# SunS_fixture_EGSE_FTDI.net
KiCad netlist of a schematic drawn in Altium Designer
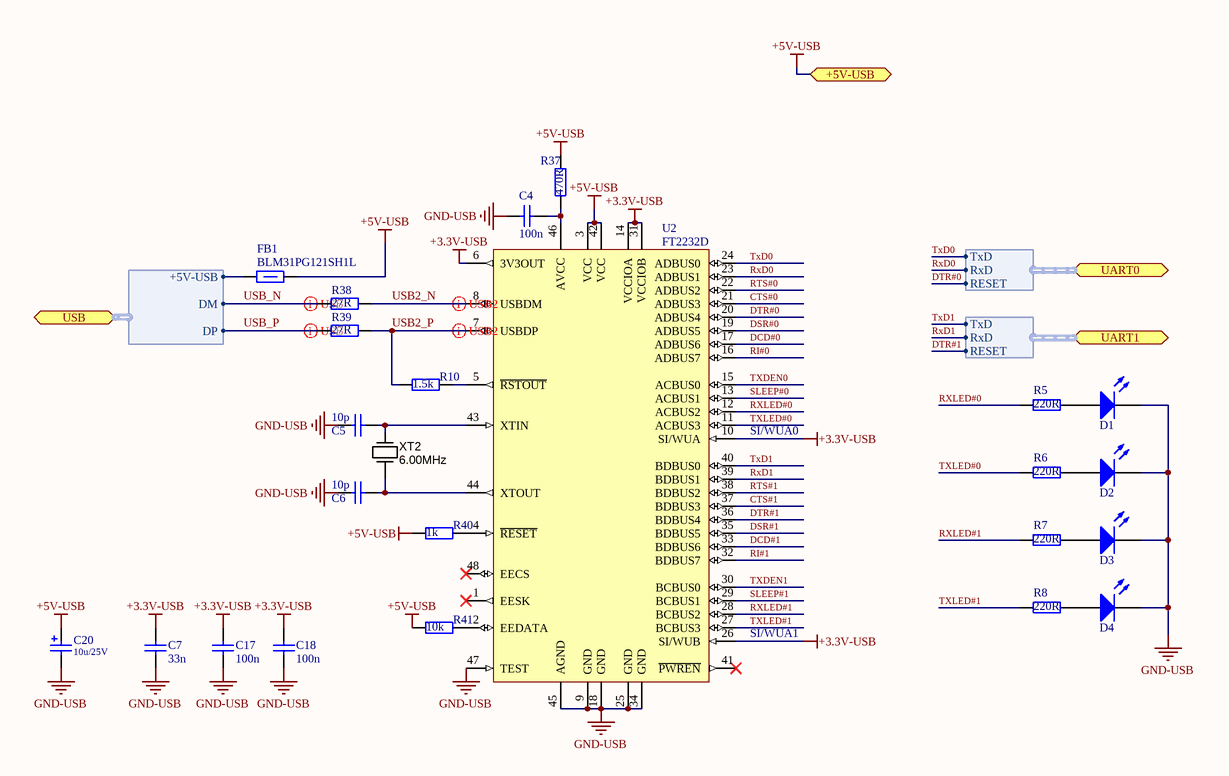
[diagram p0: SunS_fixture_EGSE_FTDI.SchDoc]

(export (version "E")
  (design (tool "Eeschema 10.0.6"))
  (components
    (comp (ref "C4")
      (value "100n")
      (footprint "SMD_Capacitor_0603")
      (description "Cap")
      (libsource (lib "capacitors") (part "Cap"))
    )
    (comp (ref "C5")
      (value "10p")
      (footprint "SMD_Capacitor_0603")
      (description "Cap")
      (libsource (lib "capacitors") (part "Cap"))
    )
    (comp (ref "C6")
      (value "10p")
      (footprint "SMD_Capacitor_0603")
      (description "Cap")
      (libsource (lib "capacitors") (part "Cap"))
    )
    (comp (ref "C7")
      (value "33n")
      (footprint "SMD_Capacitor_0603")
      (description "Cap")
      (libsource (lib "capacitors") (part "Cap"))
    )
    (comp (ref "C17")
      (value "100n")
      (footprint "SMD_Capacitor_0603")
      (description "Cap")
      (libsource (lib "capacitors") (part "Cap"))
    )
    (comp (ref "C18")
      (value "100n")
      (footprint "SMD_Capacitor_0603")
      (description "Cap")
      (libsource (lib "capacitors") (part "Cap"))
    )
    (comp (ref "C20")
      (value "10u/25V")
      (footprint "Tantalum_cap_D")
      (description "Tantalum Capacitor CWR11 10u/22V.")
      (fields
        (field (name "MANUFACTURERPARTNUMBER") "CWR11K(6)106(1)(2)(5)")
        (field (name "MANUFACTURER") "Kemet")
      )
      (libsource (lib "capacitors") (part "TantS_CWR11_10u_25V"))
    )
    (comp (ref "D1")
      (value "LEDX")
      (footprint "LED 0805 RED")
      (description "Typical LED")
      (libsource (lib "diodes") (part "LEDX"))
    )
    (comp (ref "D2")
      (value "LEDX")
      (footprint "LED 0805 RED")
      (description "Typical LED")
      (libsource (lib "diodes") (part "LEDX"))
    )
    (comp (ref "D3")
      (value "LEDX")
      (footprint "LED 0805 RED")
      (description "Typical LED")
      (libsource (lib "diodes") (part "LEDX"))
    )
    (comp (ref "D4")
      (value "LEDX")
      (footprint "LED 0805 RED")
      (description "Typical LED")
      (libsource (lib "diodes") (part "LEDX"))
    )
    (comp (ref "FB1")
      (value "120R/100MHz")
      (footprint "SMD_FerriteBead_1206")
      (description "Ferrite bead, 1206, 0.02HM, 3.5A.")
      (fields (field (name "MANUFACTURER") "Murata") (field (name "MANUFACTURERPARTNUMBER") "BLM31PG121SH1L"))
      (libsource (lib "inductors") (part "BLM31PG121SH1L"))
    )
    (comp (ref "R5")
      (value "220R")
      (footprint "SMD_Resistor_0603")
      (libsource (lib "resistors") (part "Res"))
    )
    (comp (ref "R6")
      (value "220R")
      (footprint "SMD_Resistor_0603")
      (libsource (lib "resistors") (part "Res"))
    )
    (comp (ref "R7")
      (value "220R")
      (footprint "SMD_Resistor_0603")
      (libsource (lib "resistors") (part "Res"))
    )
    (comp (ref "R8")
      (value "220R")
      (footprint "SMD_Resistor_0603")
      (libsource (lib "resistors") (part "Res"))
    )
    (comp (ref "R10")
      (value "1.5k")
      (footprint "SMD_Resistor_0603")
      (libsource (lib "resistors") (part "Res"))
    )
    (comp (ref "R37") (value "470R") (footprint "SMD_Resistor_0603") (libsource (lib "") (part "Res_1")))
    (comp (ref "R38") (value "27R") (footprint "SMD_Resistor_0603") (libsource (lib "") (part "Res_2")))
    (comp (ref "R39") (value "27R") (footprint "SMD_Resistor_0603") (libsource (lib "") (part "Res_2")))
    (comp (ref "R40") (value "1k") (footprint "SMD_Resistor_0603") (libsource (lib "resistors") (part "Res")))
    (comp (ref "R41")
      (value "10k")
      (footprint "SMD_Resistor_0603")
      (libsource (lib "resistors") (part "Res"))
    )
    (comp (ref "U2")
      (value "FT2232D")
      (footprint "LQFP-48_N")
      (description "FT2232D Dual USB to Serial UART/FIFO IC, -40 to +85 degC, 48-pin LQFP")
      (fields (field (name "MANUFACTURER") "FTDI"))
      (libsource (lib "FTDI FT Series") (part "FT2232D"))
    )
    (comp (ref "XT2")
      (value "6.00MHz")
      (footprint "HC49U")
      (description "Resonator Ceramic")
      (fields (field (name "TOLERANCE") "±50ppm"))
      (libsource (lib "crystal") (part "Crystal"))
    )
  )
  (nets
    (net (code "3") (name "+3.3V-USB") (class "Default")
      (node (ref "C17") (pin "1") (pinfunction "1_1") (pintype "passive"))
      (node (ref "C18") (pin "1") (pinfunction "1_1") (pintype "passive"))
      (node (ref "C7") (pin "1") (pinfunction "1_1") (pintype "passive"))
      (node (ref "U2") (pin "10") (pinfunction "SI/WUA_10") (pintype "input"))
      (node (ref "U2") (pin "14") (pinfunction "VCCIOA_14") (pintype "power_in"))
      (node (ref "U2") (pin "26") (pinfunction "SI/WUB_26") (pintype "input"))
      (node (ref "U2") (pin "31") (pinfunction "VCCIOB_31") (pintype "power_in"))
      (node (ref "U2") (pin "6") (pinfunction "3V3OUT_6") (pintype "output"))
    )
    (net (code "4") (name "+5V-USB") (class "Default")
      (node (ref "C20") (pin "1") (pinfunction "1_1") (pintype "passive"))
      (node (ref "FB1") (pin "1") (pinfunction "1_1") (pintype "passive"))
      (node (ref "R37") (pin "2") (pinfunction "2_2") (pintype "passive"))
      (node (ref "R40") (pin "1") (pinfunction "1_1") (pintype "passive"))
      (node (ref "R41") (pin "1") (pinfunction "1_1") (pintype "passive"))
      (node (ref "U2") (pin "3") (pinfunction "VCC_3") (pintype "power_in"))
      (node (ref "U2") (pin "42") (pinfunction "VCC_42") (pintype "power_in"))
    )
    (net (code "5") (name "/CTS#0") (class "Default")
      (node (ref "U2") (pin "21") (pinfunction "ADBUS3_21") (pintype "bidirectional"))
    )
    (net (code "6") (name "/CTS#1") (class "Default")
      (node (ref "U2") (pin "37") (pinfunction "BDBUS3_37") (pintype "bidirectional"))
    )
    (net (code "7") (name "/DCD#0") (class "Default")
      (node (ref "U2") (pin "17") (pinfunction "ADBUS6_17") (pintype "bidirectional"))
    )
    (net (code "8") (name "/DCD#1") (class "Default")
      (node (ref "U2") (pin "33") (pinfunction "BDBUS6_33") (pintype "bidirectional"))
    )
    (net (code "9") (name "/DSR#0") (class "Default")
      (node (ref "U2") (pin "19") (pinfunction "ADBUS5_19") (pintype "bidirectional"))
    )
    (net (code "10") (name "/DSR#1") (class "Default")
      (node (ref "U2") (pin "35") (pinfunction "BDBUS5_35") (pintype "bidirectional"))
    )
    (net (code "11") (name "/DTR#0") (class "Default")
      (node (ref "U2") (pin "20") (pinfunction "ADBUS4_20") (pintype "bidirectional"))
    )
    (net (code "12") (name "/DTR#1") (class "Default")
      (node (ref "U2") (pin "36") (pinfunction "BDBUS4_36") (pintype "bidirectional"))
    )
    (net (code "13") (name "/RI#0") (class "Default")
      (node (ref "U2") (pin "16") (pinfunction "ADBUS7_16") (pintype "bidirectional"))
    )
    (net (code "14") (name "/RI#1") (class "Default")
      (node (ref "U2") (pin "32") (pinfunction "BDBUS7_32") (pintype "bidirectional"))
    )
    (net (code "15") (name "/RTS#0") (class "Default")
      (node (ref "U2") (pin "22") (pinfunction "ADBUS2_22") (pintype "bidirectional"))
    )
    (net (code "16") (name "/RTS#1") (class "Default")
      (node (ref "U2") (pin "38") (pinfunction "BDBUS2_38") (pintype "bidirectional"))
    )
    (net (code "17") (name "/RXLED#0") (class "Default")
      (node (ref "R5") (pin "1") (pinfunction "1_1") (pintype "passive"))
      (node (ref "U2") (pin "12") (pinfunction "ACBUS2_12") (pintype "bidirectional"))
    )
    (net (code "18") (name "/RXLED#1") (class "Default")
      (node (ref "R7") (pin "1") (pinfunction "1_1") (pintype "passive"))
      (node (ref "U2") (pin "28") (pinfunction "BCBUS2_28") (pintype "bidirectional"))
    )
    (net (code "19") (name "/RxD0") (class "Default")
      (node (ref "U2") (pin "23") (pinfunction "ADBUS1_23") (pintype "bidirectional"))
    )
    (net (code "20") (name "/RxD1") (class "Default")
      (node (ref "U2") (pin "39") (pinfunction "BDBUS1_39") (pintype "bidirectional"))
    )
    (net (code "21") (name "/SLEEP#0") (class "Default")
      (node (ref "U2") (pin "13") (pinfunction "ACBUS1_13") (pintype "bidirectional"))
    )
    (net (code "22") (name "/SLEEP#1") (class "Default")
      (node (ref "U2") (pin "29") (pinfunction "BCBUS1_29") (pintype "bidirectional"))
    )
    (net (code "23") (name "/TXDEN0") (class "Default")
      (node (ref "U2") (pin "15") (pinfunction "ACBUS0_15") (pintype "bidirectional"))
    )
    (net (code "24") (name "/TXDEN1") (class "Default")
      (node (ref "U2") (pin "30") (pinfunction "BCBUS0_30") (pintype "bidirectional"))
    )
    (net (code "25") (name "/TXLED#0") (class "Default")
      (node (ref "R6") (pin "1") (pinfunction "1_1") (pintype "passive"))
      (node (ref "U2") (pin "11") (pinfunction "ACBUS3_11") (pintype "bidirectional"))
    )
    (net (code "26") (name "/TXLED#1") (class "Default")
      (node (ref "R8") (pin "1") (pinfunction "1_1") (pintype "passive"))
      (node (ref "U2") (pin "27") (pinfunction "BCBUS3_27") (pintype "bidirectional"))
    )
    (net (code "27") (name "/TxD0") (class "Default")
      (node (ref "U2") (pin "24") (pinfunction "ADBUS0_24") (pintype "bidirectional"))
    )
    (net (code "28") (name "/TxD1") (class "Default")
      (node (ref "U2") (pin "40") (pinfunction "BDBUS0_40") (pintype "bidirectional"))
    )
    (net (code "29") (name "/USB2_N") (class "Default")
      (node (ref "R38") (pin "1") (pinfunction "1_1") (pintype "passive"))
      (node (ref "U2") (pin "8") (pinfunction "USBDM_8") (pintype "bidirectional"))
    )
    (net (code "30") (name "/USB2_P") (class "Default")
      (node (ref "R10") (pin "1") (pinfunction "1_1") (pintype "passive"))
      (node (ref "R39") (pin "1") (pinfunction "1_1") (pintype "passive"))
      (node (ref "U2") (pin "7") (pinfunction "USBDP_7") (pintype "bidirectional"))
    )
    (net (code "31") (name "/USB_N") (class "Default")
      (node (ref "R38") (pin "2") (pinfunction "2_2") (pintype "passive"))
    )
    (net (code "32") (name "/USB_P") (class "Default")
      (node (ref "R39") (pin "2") (pinfunction "2_2") (pintype "passive"))
    )
    (net (code "35") (name "GND-USB") (class "Default")
      (node (ref "C17") (pin "2") (pinfunction "2_2") (pintype "passive"))
      (node (ref "C18") (pin "2") (pinfunction "2_2") (pintype "passive"))
      (node (ref "C20") (pin "2") (pinfunction "2_2") (pintype "passive"))
      (node (ref "C4") (pin "2") (pinfunction "2_2") (pintype "passive"))
      (node (ref "C5") (pin "2") (pinfunction "2_2") (pintype "passive"))
      (node (ref "C6") (pin "2") (pinfunction "2_2") (pintype "passive"))
      (node (ref "C7") (pin "2") (pinfunction "2_2") (pintype "passive"))
      (node (ref "D1") (pin "2") (pinfunction "K_2") (pintype "passive"))
      (node (ref "D2") (pin "2") (pinfunction "K_2") (pintype "passive"))
      (node (ref "D3") (pin "2") (pinfunction "K_2") (pintype "passive"))
      (node (ref "D4") (pin "2") (pinfunction "K_2") (pintype "passive"))
      (node (ref "U2") (pin "18") (pinfunction "GND_18") (pintype "power_in"))
      (node (ref "U2") (pin "25") (pinfunction "GND_25") (pintype "power_in"))
      (node (ref "U2") (pin "34") (pinfunction "GND_34") (pintype "power_in"))
      (node (ref "U2") (pin "45") (pinfunction "AGND_45") (pintype "power_in"))
      (node (ref "U2") (pin "47") (pinfunction "TEST_47") (pintype "input"))
      (node (ref "U2") (pin "9") (pinfunction "GND_9") (pintype "power_in"))
    )
    (net (code "36") (name "Net-(D1-A)") (class "Default")
      (node (ref "D1") (pin "1") (pinfunction "A_1") (pintype "passive"))
      (node (ref "R5") (pin "2") (pinfunction "2_2") (pintype "passive"))
    )
    (net (code "37") (name "Net-(D2-A)") (class "Default")
      (node (ref "D2") (pin "1") (pinfunction "A_1") (pintype "passive"))
      (node (ref "R6") (pin "2") (pinfunction "2_2") (pintype "passive"))
    )
    (net (code "38") (name "Net-(D3-A)") (class "Default")
      (node (ref "D3") (pin "1") (pinfunction "A_1") (pintype "passive"))
      (node (ref "R7") (pin "2") (pinfunction "2_2") (pintype "passive"))
    )
    (net (code "39") (name "Net-(D4-A)") (class "Default")
      (node (ref "D4") (pin "1") (pinfunction "A_1") (pintype "passive"))
      (node (ref "R8") (pin "2") (pinfunction "2_2") (pintype "passive"))
    )
    (net (code "40") (name "Net-(U2-AVCC)") (class "Default")
      (node (ref "C4") (pin "1") (pinfunction "1_1") (pintype "passive"))
      (node (ref "R37") (pin "1") (pinfunction "1_1") (pintype "passive"))
      (node (ref "U2") (pin "46") (pinfunction "AVCC_46") (pintype "power_in"))
    )
    (net (code "41") (name "Net-(U2-EEDATA)") (class "Default")
      (node (ref "R41") (pin "2") (pinfunction "2_2") (pintype "passive"))
      (node (ref "U2") (pin "2") (pinfunction "EEDATA_2") (pintype "bidirectional"))
    )
    (net (code "42") (name "Net-(U2-XTIN)") (class "Default")
      (node (ref "C5") (pin "1") (pinfunction "1_1") (pintype "passive"))
      (node (ref "U2") (pin "43") (pinfunction "XTIN_43") (pintype "input"))
      (node (ref "XT2") (pin "2") (pinfunction "OUT_2") (pintype "passive"))
    )
    (net (code "43") (name "Net-(U2-XTOUT)") (class "Default")
      (node (ref "C6") (pin "1") (pinfunction "1_1") (pintype "passive"))
      (node (ref "U2") (pin "44") (pinfunction "XTOUT_44") (pintype "output"))
      (node (ref "XT2") (pin "1") (pinfunction "IN_1") (pintype "passive"))
    )
    (net (code "44") (name "Net-(U2-~{RESET})") (class "Default")
      (node (ref "R40") (pin "2") (pinfunction "2_2") (pintype "passive"))
      (node (ref "U2") (pin "4") (pinfunction "~{RESET}_4") (pintype "input"))
    )
    (net (code "45") (name "Net-(U2-~{RSTOUT})") (class "Default")
      (node (ref "R10") (pin "2") (pinfunction "2_2") (pintype "passive"))
      (node (ref "U2") (pin "5") (pinfunction "~{RSTOUT}_5") (pintype "output"))
    )
    (net (code "46") (name "unconnected-(FB1-Pad2)") (class "Default")
      (node (ref "FB1") (pin "2") (pinfunction "2_2") (pintype "passive"))
    )
    (net (code "47") (name "unconnected-(U2-EECS-Pad48)") (class "Default")
      (node (ref "U2") (pin "48") (pinfunction "EECS_48") (pintype "bidirectional+no_connect"))
    )
    (net (code "48") (name "unconnected-(U2-EESK-Pad1)") (class "Default")
      (node (ref "U2") (pin "1") (pinfunction "EESK_1") (pintype "output+no_connect"))
    )
    (net (code "49") (name "unconnected-(U2-~{PWREN}-Pad41)") (class "Default")
      (node (ref "U2") (pin "41") (pinfunction "~{PWREN}_41") (pintype "output+no_connect"))
    )
  )
)
